# 2020-08-19_08-57-041.net
KiCad netlist of a schematic drawn in Altium Designer
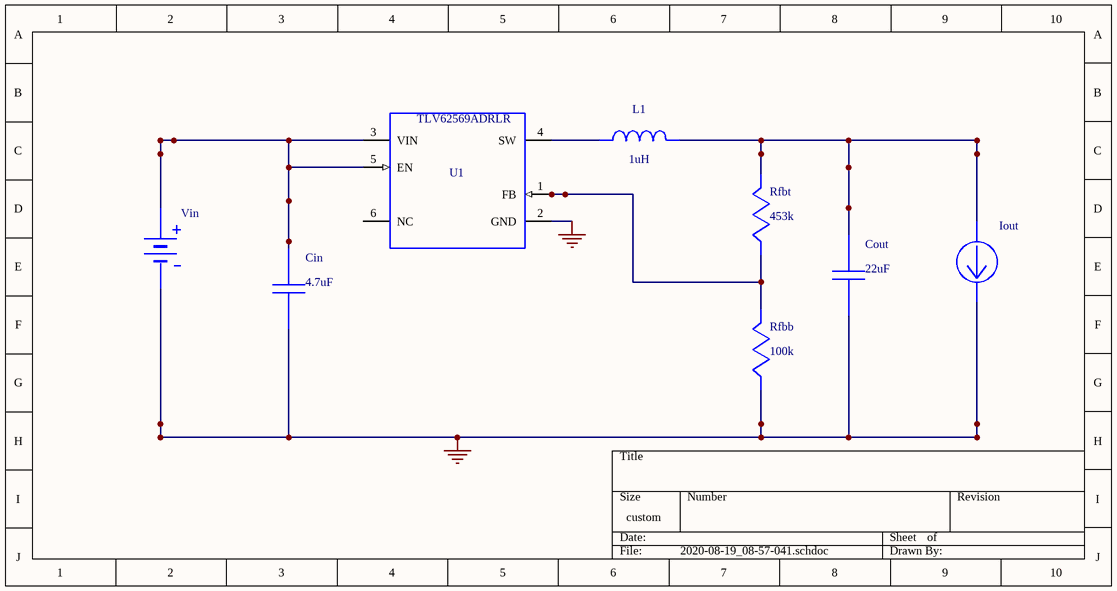
[diagram p0: 2020-08-19_08-57-041.schdoc]

(export (version "E")
  (design (tool "Eeschema 10.0.6"))
  (components
    (comp (ref "Cin")
      (value "4.7uF")
      (description "C1608X7S1A475K08")
      (fields (field (name "MANUFACTURER PART NUMBER") "C1608X7S1A475K080AC"))
      (libsource (lib "TI WEBENCH") (part "Cin"))
    )
    (comp (ref "Cout")
      (value "22uF")
      (description "GRM188R60J226MEA")
      (fields (field (name "MANUFACTURER PART NUMBER") "GRM188R60J226MEA0D"))
      (libsource (lib "TI WEBENCH") (part "Cout"))
    )
    (comp (ref "Iout") (value "WB_CURRENT_LOAD") (libsource (lib "TI WEBENCH") (part "Iout")))
    (comp (ref "L1") (value "1uH") (description "SRN8040-1R0Y") (libsource (lib "TI WEBENCH") (part "L1")))
    (comp (ref "Rfbb")
      (value "100k")
      (description "CRCW0402100KFKED")
      (libsource (lib "TI WEBENCH") (part "Rfbb"))
    )
    (comp (ref "Rfbt")
      (value "453k")
      (description "CRCW0402453KFKED")
      (libsource (lib "TI WEBENCH") (part "Rfbt"))
    )
    (comp (ref "U1")
      (value "TLV62569ADRLR")
      (fields (field (name "PACKAGEREFERENCE") "TLV62569ADRLR"))
      (libsource (lib "TI WEBENCH") (part "U1"))
    )
    (comp (ref "Vin") (value "WB_BATTERY") (libsource (lib "TI WEBENCH") (part "Vin")))
  )
  (nets
    (net (code "1") (name "0") (class "Default")
      (node (ref "Cin") (pin "2") (pinfunction "2_2") (pintype "passive"))
      (node (ref "Cout") (pin "2") (pinfunction "2_2") (pintype "passive"))
      (node (ref "Iout") (pin "2") (pinfunction "-_2") (pintype "passive"))
      (node (ref "Rfbb") (pin "2") (pinfunction "2_2") (pintype "passive"))
      (node (ref "U1") (pin "2") (pinfunction "GND_2") (pintype "power_in"))
      (node (ref "Vin") (pin "2") (pinfunction "-_2") (pintype "passive"))
    )
    (net (code "2") (name "Net-(Iout-+)") (class "Default")
      (node (ref "Cout") (pin "1") (pinfunction "1_1") (pintype "passive"))
      (node (ref "Iout") (pin "1") (pinfunction "+_1") (pintype "passive"))
      (node (ref "L1") (pin "2") (pinfunction "2_2") (pintype "passive"))
      (node (ref "Rfbt") (pin "1") (pinfunction "1_1") (pintype "passive"))
    )
    (net (code "3") (name "Net-(U1-EN)") (class "Default")
      (node (ref "Cin") (pin "1") (pinfunction "1_1") (pintype "passive"))
      (node (ref "U1") (pin "3") (pinfunction "VIN_3") (pintype "power_in"))
      (node (ref "U1") (pin "5") (pinfunction "EN_5") (pintype "input"))
      (node (ref "Vin") (pin "1") (pinfunction "+_1") (pintype "passive"))
    )
    (net (code "4") (name "Net-(U1-FB)") (class "Default")
      (node (ref "Rfbb") (pin "1") (pinfunction "1_1") (pintype "passive"))
      (node (ref "Rfbt") (pin "2") (pinfunction "2_2") (pintype "passive"))
      (node (ref "U1") (pin "1") (pinfunction "FB_1") (pintype "input"))
    )
    (net (code "5") (name "Net-(U1-SW)") (class "Default")
      (node (ref "L1") (pin "1") (pinfunction "1_1") (pintype "passive"))
      (node (ref "U1") (pin "4") (pinfunction "SW_4") (pintype "power_in"))
    )
    (net (code "6") (name "unconnected-(U1-NC-Pad6)") (class "Default")
      (node (ref "U1") (pin "6") (pinfunction "NC_6") (pintype "passive"))
    )
  )
)
